# energyAnalizer.net
KiCad netlist of a schematic drawn in Altium Designer
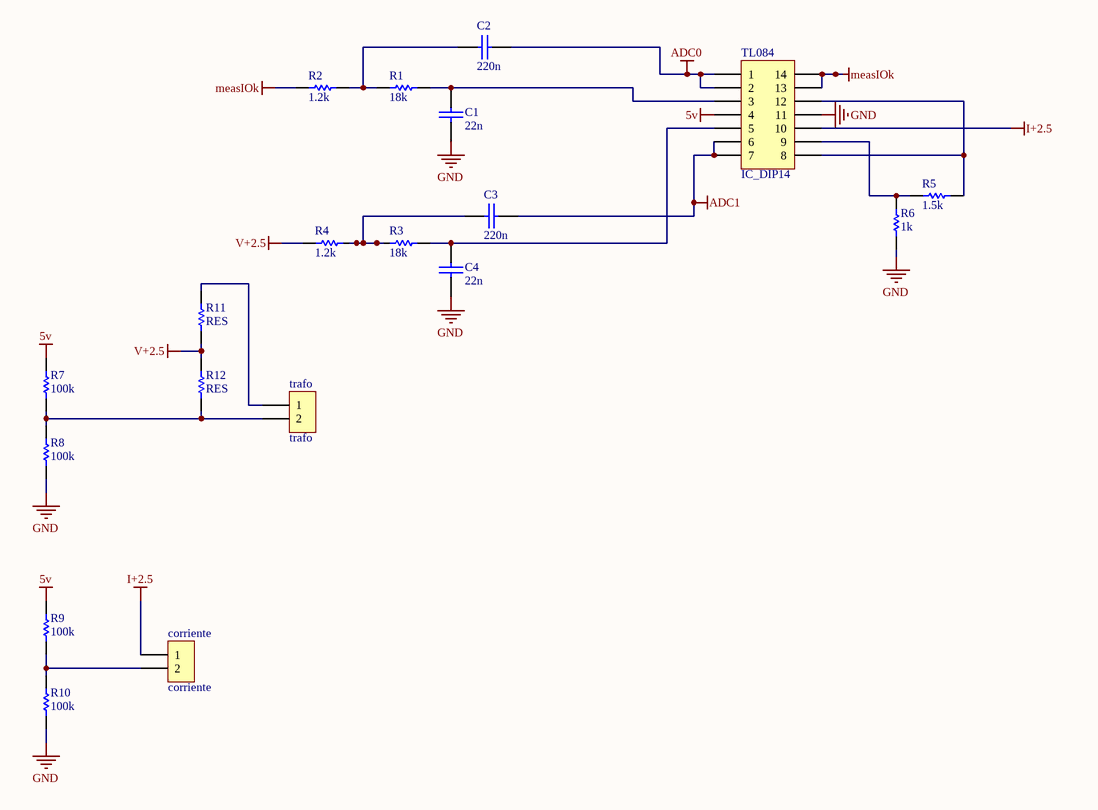
[diagram p0: energyAnalizer.SchDoc]

(export (version "E")
  (design (tool "Eeschema 10.0.6"))
  (components
    (comp (ref "C1") (value "22n") (footprint "CAP200") (libsource (lib "LIBEBAL") (part "CAP")))
    (comp (ref "C2") (value "220n") (footprint "CAP200") (libsource (lib "LIBEBAL") (part "CAP")))
    (comp (ref "C3") (value "220n") (footprint "CAP200") (libsource (lib "LIBEBAL") (part "CAP")))
    (comp (ref "C4") (value "22n") (footprint "CAP200") (libsource (lib "LIBEBAL") (part "CAP")))
    (comp (ref "corriente")
      (value "corriente")
      (footprint "BORNERA2")
      (libsource (lib "LIBEBAL") (part "BORNERA 2"))
    )
    (comp (ref "R1") (value "18k") (footprint "RES400") (libsource (lib "LIBEBAL") (part "RES")))
    (comp (ref "R2") (value "1.2k") (footprint "RES400") (libsource (lib "LIBEBAL") (part "RES")))
    (comp (ref "R3") (value "18k") (footprint "RES400") (libsource (lib "LIBEBAL") (part "RES")))
    (comp (ref "R4") (value "1.2k") (footprint "RES400") (libsource (lib "LIBEBAL") (part "RES")))
    (comp (ref "R5") (value "1.5k") (footprint "RES400") (libsource (lib "LIBEBAL") (part "RES")))
    (comp (ref "R6") (value "1k") (footprint "RES400") (libsource (lib "LIBEBAL") (part "RES")))
    (comp (ref "R7") (value "100k") (footprint "RES400") (libsource (lib "LIBEBAL") (part "RES")))
    (comp (ref "R8") (value "100k") (footprint "RES400") (libsource (lib "LIBEBAL") (part "RES")))
    (comp (ref "R9") (value "100k") (footprint "RES400") (libsource (lib "LIBEBAL") (part "RES")))
    (comp (ref "R10") (value "100k") (footprint "RES400") (libsource (lib "LIBEBAL") (part "RES")))
    (comp (ref "R11") (value "RES") (footprint "RES400") (libsource (lib "LIBEBAL") (part "RES")))
    (comp (ref "R12") (value "RES") (footprint "RES400") (libsource (lib "LIBEBAL") (part "RES")))
    (comp (ref "TL084") (value "IC_DIP14") (footprint "DIP14") (libsource (lib "LIBEBAL") (part "IC_DIP14")))
    (comp (ref "trafo") (value "trafo") (footprint "BORNERA2") (libsource (lib "LIBEBAL") (part "BORNERA 2")))
  )
  (nets
    (net (code "1") (name "5v") (class "Default")
      (node (ref "R7") (pin "2") (pinfunction "2_2") (pintype "passive"))
      (node (ref "R9") (pin "2") (pinfunction "2_2") (pintype "passive"))
      (node (ref "TL084") (pin "4") (pinfunction "4_4") (pintype "passive"))
    )
    (net (code "2") (name "ADC0") (class "Default")
      (node (ref "C2") (pin "2") (pinfunction "2_2") (pintype "passive"))
      (node (ref "TL084") (pin "1") (pinfunction "1_1") (pintype "passive"))
      (node (ref "TL084") (pin "2") (pinfunction "2_2") (pintype "passive"))
    )
    (net (code "3") (name "ADC1") (class "Default")
      (node (ref "C3") (pin "2") (pinfunction "2_2") (pintype "passive"))
      (node (ref "TL084") (pin "6") (pinfunction "6_6") (pintype "passive"))
      (node (ref "TL084") (pin "7") (pinfunction "7_7") (pintype "passive"))
    )
    (net (code "4") (name "GND") (class "Default")
      (node (ref "C1") (pin "2") (pinfunction "2_2") (pintype "passive"))
      (node (ref "C4") (pin "1") (pinfunction "1_1") (pintype "passive"))
      (node (ref "R10") (pin "1") (pinfunction "1_1") (pintype "passive"))
      (node (ref "R6") (pin "1") (pinfunction "1_1") (pintype "passive"))
      (node (ref "R8") (pin "1") (pinfunction "1_1") (pintype "passive"))
      (node (ref "TL084") (pin "11") (pinfunction "11_11") (pintype "passive"))
    )
    (net (code "5") (name "I+2.5") (class "Default")
      (node (ref "TL084") (pin "10") (pinfunction "10_10") (pintype "passive"))
      (node (ref "corriente") (pin "1") (pinfunction "1_1") (pintype "passive"))
    )
    (net (code "6") (name "Net-(C1-Pad1)") (class "Default")
      (node (ref "C1") (pin "1") (pinfunction "1_1") (pintype "passive"))
      (node (ref "R1") (pin "2") (pinfunction "2_2") (pintype "passive"))
      (node (ref "TL084") (pin "3") (pinfunction "3_3") (pintype "passive"))
    )
    (net (code "7") (name "Net-(C2-Pad1)") (class "Default")
      (node (ref "C2") (pin "1") (pinfunction "1_1") (pintype "passive"))
      (node (ref "R1") (pin "1") (pinfunction "1_1") (pintype "passive"))
      (node (ref "R2") (pin "2") (pinfunction "2_2") (pintype "passive"))
    )
    (net (code "8") (name "Net-(C3-Pad1)") (class "Default")
      (node (ref "C3") (pin "1") (pinfunction "1_1") (pintype "passive"))
      (node (ref "R3") (pin "1") (pinfunction "1_1") (pintype "passive"))
      (node (ref "R4") (pin "2") (pinfunction "2_2") (pintype "passive"))
    )
    (net (code "9") (name "Net-(C4-Pad2)") (class "Default")
      (node (ref "C4") (pin "2") (pinfunction "2_2") (pintype "passive"))
      (node (ref "R3") (pin "2") (pinfunction "2_2") (pintype "passive"))
      (node (ref "TL084") (pin "5") (pinfunction "5_5") (pintype "passive"))
    )
    (net (code "10") (name "Net-(R5-Pad1)") (class "Default")
      (node (ref "R5") (pin "1") (pinfunction "1_1") (pintype "passive"))
      (node (ref "R6") (pin "2") (pinfunction "2_2") (pintype "passive"))
      (node (ref "TL084") (pin "9") (pinfunction "9_9") (pintype "passive"))
    )
    (net (code "11") (name "Net-(R5-Pad2)") (class "Default")
      (node (ref "R5") (pin "2") (pinfunction "2_2") (pintype "passive"))
      (node (ref "TL084") (pin "12") (pinfunction "12_12") (pintype "passive"))
      (node (ref "TL084") (pin "8") (pinfunction "8_8") (pintype "passive"))
    )
    (net (code "12") (name "Net-(R10-Pad2)") (class "Default")
      (node (ref "R10") (pin "2") (pinfunction "2_2") (pintype "passive"))
      (node (ref "R9") (pin "1") (pinfunction "1_1") (pintype "passive"))
      (node (ref "corriente") (pin "2") (pinfunction "2_2") (pintype "passive"))
    )
    (net (code "13") (name "Net-(R11-Pad2)") (class "Default")
      (node (ref "R11") (pin "2") (pinfunction "2_2") (pintype "passive"))
      (node (ref "trafo") (pin "1") (pinfunction "1_1") (pintype "passive"))
    )
    (net (code "14") (name "Net-(R12-Pad1)") (class "Default")
      (node (ref "R12") (pin "1") (pinfunction "1_1") (pintype "passive"))
      (node (ref "R7") (pin "1") (pinfunction "1_1") (pintype "passive"))
      (node (ref "R8") (pin "2") (pinfunction "2_2") (pintype "passive"))
      (node (ref "trafo") (pin "2") (pinfunction "2_2") (pintype "passive"))
    )
    (net (code "15") (name "V+2.5") (class "Default")
      (node (ref "R11") (pin "1") (pinfunction "1_1") (pintype "passive"))
      (node (ref "R12") (pin "2") (pinfunction "2_2") (pintype "passive"))
      (node (ref "R4") (pin "1") (pinfunction "1_1") (pintype "passive"))
    )
    (net (code "16") (name "measIOk") (class "Default")
      (node (ref "R2") (pin "1") (pinfunction "1_1") (pintype "passive"))
      (node (ref "TL084") (pin "13") (pinfunction "13_13") (pintype "passive"))
      (node (ref "TL084") (pin "14") (pinfunction "14_14") (pintype "passive"))
    )
  )
)
